# llrf_afe_pwr_ctrl.net
KiCad netlist of a schematic drawn in Altium Designer
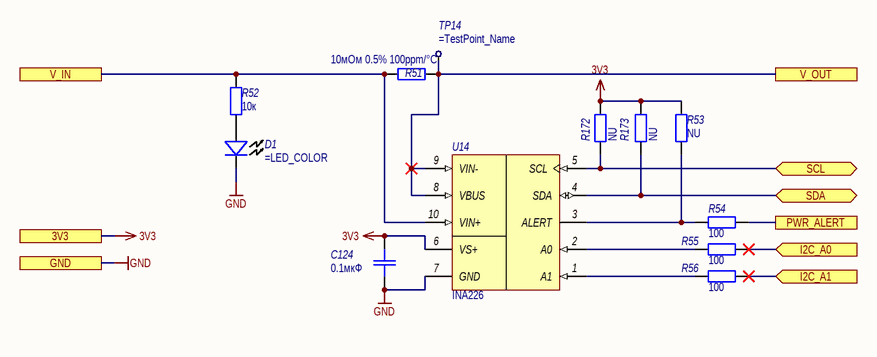
[diagram p0: llrf_afe_pwr_ctrl.SchDoc]

(export (version "E")
  (design (tool "Eeschema 10.0.6"))
  (components
    (comp (ref "C124")
      (value "0.1мкФ")
      (footprint "SMD_C0402")
      (description "Capacitor")
      (libsource (lib "Passive") (part "Capacitor"))
    )
    (comp (ref "D1") (value "LED") (footprint "LED-0805") (libsource (lib "Diod") (part "LED")))
    (comp (ref "R51")
      (value "10мОм 0.5% 100ppm/°C")
      (footprint "SMD_1206")
      (description "PE1206DRM470R01L")
      (libsource (lib "Passive") (part "Resistor"))
    )
    (comp (ref "R52")
      (value "10к")
      (footprint "SMD_0603")
      (description "Resistor")
      (libsource (lib "") (part "Resistor_2"))
    )
    (comp (ref "R53")
      (value "NU")
      (footprint "SMD_0603")
      (description "Resistor")
      (libsource (lib "") (part "Resistor_1"))
    )
    (comp (ref "R54")
      (value "100")
      (footprint "SMD_0603")
      (description "Resistor")
      (libsource (lib "Passive") (part "Resistor"))
    )
    (comp (ref "R55")
      (value "100")
      (footprint "SMD_0603")
      (description "Resistor")
      (libsource (lib "Passive") (part "Resistor"))
    )
    (comp (ref "R56")
      (value "100")
      (footprint "SMD_0603")
      (description "Resistor")
      (libsource (lib "Passive") (part "Resistor"))
    )
    (comp (ref "R172")
      (value "NU")
      (footprint "SMD_0603")
      (description "Resistor")
      (libsource (lib "") (part "Resistor_1"))
    )
    (comp (ref "R173")
      (value "NU")
      (footprint "SMD_0603")
      (description "Resistor")
      (libsource (lib "") (part "Resistor_1"))
    )
    (comp (ref "TP14") (value "~") (footprint "TestPoint") (libsource (lib "Connector") (part "TP")))
    (comp (ref "U14")
      (value "INA226")
      (footprint "VSSOP-10")
      (description "High- or Low-Side Measurement, Bidirectional Current and Power Monitor With I2C Interface")
      (fields (field (name "НАИМЕНОВАНИЕ") "INA226"))
      (libsource (lib "Power_Monitor") (part "INA226"))
    )
  )
  (nets
    (net (code "1") (name "/I2C_A0") (class "Default")
      (node (ref "R55") (pin "1") (pinfunction "1_1") (pintype "passive+no_connect"))
    )
    (net (code "2") (name "/I2C_A1") (class "Default")
      (node (ref "R56") (pin "1") (pinfunction "1_1") (pintype "passive+no_connect"))
    )
    (net (code "3") (name "/PWR_ALERT") (class "Default")
      (node (ref "R54") (pin "1") (pinfunction "1_1") (pintype "passive"))
    )
    (net (code "4") (name "/SCL") (class "Default")
      (node (ref "R172") (pin "1") (pinfunction "1_1") (pintype "passive"))
      (node (ref "U14") (pin "5") (pinfunction "SCL_5") (pintype "input"))
    )
    (net (code "5") (name "/SDA") (class "Default")
      (node (ref "R173") (pin "1") (pinfunction "1_1") (pintype "passive"))
      (node (ref "U14") (pin "4") (pinfunction "SDA_4") (pintype "bidirectional"))
    )
    (net (code "6") (name "/V_IN") (class "Default")
      (node (ref "R51") (pin "2") (pinfunction "2_2") (pintype "passive"))
      (node (ref "R52") (pin "1") (pinfunction "1_1") (pintype "passive"))
      (node (ref "U14") (pin "10") (pinfunction "VIN+_10") (pintype "input"))
    )
    (net (code "7") (name "/V_OUT") (class "Default")
      (node (ref "R51") (pin "1") (pinfunction "1_1") (pintype "passive"))
      (node (ref "TP14") (pin "0") (pinfunction "TP_0") (pintype "passive"))
      (node (ref "U14") (pin "8") (pinfunction "VBUS_8") (pintype "input"))
      (node (ref "U14") (pin "9") (pinfunction "VIN-_9") (pintype "input"))
    )
    (net (code "8") (name "3V3") (class "Default")
      (node (ref "C124") (pin "2") (pinfunction "2_2") (pintype "passive"))
      (node (ref "R172") (pin "2") (pinfunction "2_2") (pintype "passive"))
      (node (ref "R173") (pin "2") (pinfunction "2_2") (pintype "passive"))
      (node (ref "R53") (pin "2") (pinfunction "2_2") (pintype "passive"))
      (node (ref "U14") (pin "6") (pinfunction "VS+_6") (pintype "power_in"))
    )
    (net (code "9") (name "GND") (class "Default")
      (node (ref "C124") (pin "1") (pinfunction "1_1") (pintype "passive"))
      (node (ref "D1") (pin "2") (pinfunction "K_2") (pintype "passive"))
      (node (ref "U14") (pin "7") (pinfunction "GND_7") (pintype "power_in"))
    )
    (net (code "10") (name "Net-(D1-A)") (class "Default")
      (node (ref "D1") (pin "1") (pinfunction "A_1") (pintype "passive"))
      (node (ref "R52") (pin "2") (pinfunction "2_2") (pintype "passive"))
    )
    (net (code "11") (name "Net-(U14-A0)") (class "Default")
      (node (ref "R55") (pin "2") (pinfunction "2_2") (pintype "passive"))
      (node (ref "U14") (pin "2") (pinfunction "A0_2") (pintype "input"))
    )
    (net (code "12") (name "Net-(U14-A1)") (class "Default")
      (node (ref "R56") (pin "2") (pinfunction "2_2") (pintype "passive"))
      (node (ref "U14") (pin "1") (pinfunction "A1_1") (pintype "input"))
    )
    (net (code "13") (name "Net-(U14-ALERT)") (class "Default")
      (node (ref "R53") (pin "1") (pinfunction "1_1") (pintype "passive"))
      (node (ref "R54") (pin "2") (pinfunction "2_2") (pintype "passive"))
      (node (ref "U14") (pin "3") (pinfunction "ALERT_3") (pintype "open_collector"))
    )
  )
)
